# 03-SROM.net
KiCad netlist of a schematic drawn in Altium Designer
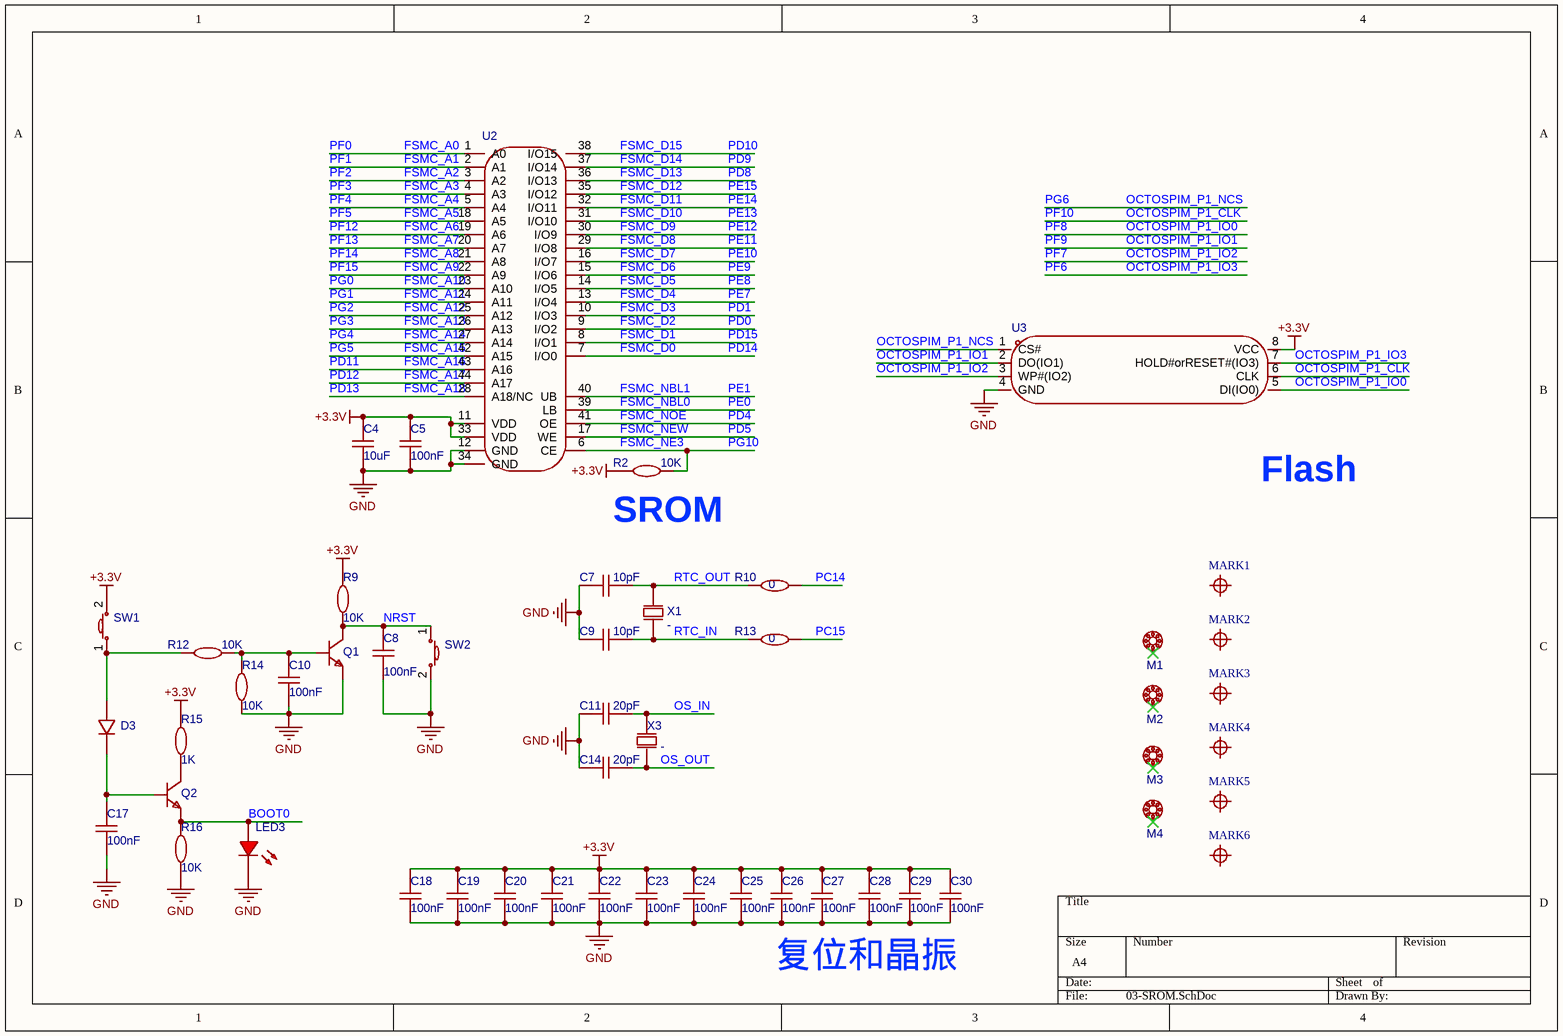
[diagram p0: 03-SROM.SchDoc]

(export (version "E")
  (design (tool "Eeschema 10.0.6"))
  (components
    (comp (ref "C4")
      (value "10uF")
      (footprint "C0603")
      (fields (field (name "Comment") "CAP_0603"))
      (libsource (lib "altium-import") (part "root_1_CAP_0603_"))
    )
    (comp (ref "C5")
      (value "100nF")
      (footprint "C0603")
      (fields (field (name "Comment") "CAP_0603"))
      (libsource (lib "altium-import") (part "root_1_CAP_0603_"))
    )
    (comp (ref "C7")
      (value "10pF")
      (footprint "C0603")
      (fields (field (name "Comment") "CAP_0603"))
      (libsource (lib "altium-import") (part "root_0_CAP_0603_"))
    )
    (comp (ref "C8")
      (value "100nF")
      (footprint "C0603")
      (fields (field (name "Comment") "CAP_0603"))
      (libsource (lib "altium-import") (part "root_1_CAP_0603_"))
    )
    (comp (ref "C9")
      (value "10pF")
      (footprint "C0603")
      (fields (field (name "Comment") "CAP_0603"))
      (libsource (lib "altium-import") (part "root_0_CAP_0603_"))
    )
    (comp (ref "C10")
      (value "100nF")
      (footprint "C0603")
      (fields (field (name "Comment") "CAP_0603"))
      (libsource (lib "altium-import") (part "root_1_CAP_0603_"))
    )
    (comp (ref "C11")
      (value "20pF")
      (footprint "C0603")
      (fields (field (name "Comment") "CAP_0603"))
      (libsource (lib "altium-import") (part "root_0_CAP_0603_"))
    )
    (comp (ref "C14")
      (value "20pF")
      (footprint "C0603")
      (fields (field (name "Comment") "CAP_0603"))
      (libsource (lib "altium-import") (part "root_0_CAP_0603_"))
    )
    (comp (ref "C17")
      (value "100nF")
      (footprint "C0603")
      (fields (field (name "Comment") "CAP_0603"))
      (libsource (lib "altium-import") (part "root_1_CAP_0603_"))
    )
    (comp (ref "C18")
      (value "100nF")
      (footprint "C0603")
      (fields (field (name "Comment") "CAP_0603"))
      (libsource (lib "altium-import") (part "root_1_CAP_0603_"))
    )
    (comp (ref "C19")
      (value "100nF")
      (footprint "C0603")
      (fields (field (name "Comment") "CAP_0603"))
      (libsource (lib "altium-import") (part "root_1_CAP_0603_"))
    )
    (comp (ref "C20")
      (value "100nF")
      (footprint "C0603")
      (fields (field (name "Comment") "CAP_0603"))
      (libsource (lib "altium-import") (part "root_1_CAP_0603_"))
    )
    (comp (ref "C21")
      (value "100nF")
      (footprint "C0603")
      (fields (field (name "Comment") "CAP_0603"))
      (libsource (lib "altium-import") (part "root_1_CAP_0603_"))
    )
    (comp (ref "C22")
      (value "100nF")
      (footprint "C0603")
      (fields (field (name "Comment") "CAP_0603"))
      (libsource (lib "altium-import") (part "root_1_CAP_0603_"))
    )
    (comp (ref "C23")
      (value "100nF")
      (footprint "C0603")
      (fields (field (name "Comment") "CAP_0603"))
      (libsource (lib "altium-import") (part "root_1_CAP_0603_"))
    )
    (comp (ref "C24")
      (value "100nF")
      (footprint "C0603")
      (fields (field (name "Comment") "CAP_0603"))
      (libsource (lib "altium-import") (part "root_1_CAP_0603_"))
    )
    (comp (ref "C25")
      (value "100nF")
      (footprint "C0603")
      (fields (field (name "Comment") "CAP_0603"))
      (libsource (lib "altium-import") (part "root_1_CAP_0603_"))
    )
    (comp (ref "C26")
      (value "100nF")
      (footprint "C0603")
      (fields (field (name "Comment") "CAP_0603"))
      (libsource (lib "altium-import") (part "root_1_CAP_0603_"))
    )
    (comp (ref "C27")
      (value "100nF")
      (footprint "C0603")
      (fields (field (name "Comment") "CAP_0603"))
      (libsource (lib "altium-import") (part "root_1_CAP_0603_"))
    )
    (comp (ref "C28")
      (value "100nF")
      (footprint "C0603")
      (fields (field (name "Comment") "CAP_0603"))
      (libsource (lib "altium-import") (part "root_1_CAP_0603_"))
    )
    (comp (ref "C29")
      (value "100nF")
      (footprint "C0603")
      (fields (field (name "Comment") "CAP_0603"))
      (libsource (lib "altium-import") (part "root_1_CAP_0603_"))
    )
    (comp (ref "C30")
      (value "100nF")
      (footprint "C0603")
      (fields (field (name "Comment") "CAP_0603"))
      (libsource (lib "altium-import") (part "root_1_CAP_0603_"))
    )
    (comp (ref "D3")
      (value "LL4148_C9808")
      (footprint "LL-34_L3.5-W1.5-RD")
      (fields (field (name "MANUFACTURER") "ST(先科)") (field (name "MANUFACTURERPART") "LL4148"))
      (libsource (lib "altium-import") (part "root_1_LL4148_C9808_"))
    )
    (comp (ref "LED3")
      (value "LED_0603-R")
      (footprint "LED_0603")
      (libsource (lib "altium-import") (part "root_3_LED_0603-R_"))
    )
    (comp (ref "M1")
      (value "M3螺丝")
      (footprint "Screw")
      (libsource (lib "altium-import") (part "root_1_M3螺丝_"))
    )
    (comp (ref "M2")
      (value "M3螺丝")
      (footprint "Screw")
      (libsource (lib "altium-import") (part "root_1_M3螺丝_"))
    )
    (comp (ref "M3")
      (value "M3螺丝")
      (footprint "Screw")
      (libsource (lib "altium-import") (part "root_1_M3螺丝_"))
    )
    (comp (ref "M4")
      (value "M3螺丝")
      (footprint "Screw")
      (libsource (lib "altium-import") (part "root_1_M3螺丝_"))
    )
    (comp (ref "MARK1")
      (value "Mark-Point")
      (footprint "Mark-Point")
      (libsource (lib "Lib") (part "Mark-Point"))
    )
    (comp (ref "MARK2")
      (value "Mark-Point")
      (footprint "Mark-Point")
      (libsource (lib "Lib") (part "Mark-Point"))
    )
    (comp (ref "MARK3")
      (value "Mark-Point")
      (footprint "Mark-Point")
      (libsource (lib "Lib") (part "Mark-Point"))
    )
    (comp (ref "MARK4")
      (value "Mark-Point")
      (footprint "Mark-Point")
      (libsource (lib "Lib") (part "Mark-Point"))
    )
    (comp (ref "MARK5")
      (value "Mark-Point")
      (footprint "Mark-Point")
      (libsource (lib "Lib") (part "Mark-Point"))
    )
    (comp (ref "MARK6")
      (value "Mark-Point")
      (footprint "Mark-Point")
      (libsource (lib "Lib") (part "Mark-Point"))
    )
    (comp (ref "Q1")
      (value "S8050_SOT_NPN")
      (footprint "S8050_SOT-23")
      (libsource (lib "altium-import") (part "root_0_S8050_SOT_NPN_"))
    )
    (comp (ref "Q2")
      (value "S8050_SOT_NPN")
      (footprint "S8050_SOT-23")
      (libsource (lib "altium-import") (part "root_0_S8050_SOT_NPN_"))
    )
    (comp (ref "R2")
      (value "10K")
      (footprint "R0603")
      (fields (field (name "Comment") "Res_0603"))
      (libsource (lib "altium-import") (part "root_2_Res_0603_"))
    )
    (comp (ref "R9")
      (value "10K")
      (footprint "R0603")
      (fields (field (name "Comment") "Res_0603"))
      (libsource (lib "altium-import") (part "root_1_Res_0603_"))
    )
    (comp (ref "R10")
      (value "0")
      (footprint "R0402")
      (fields (field (name "Comment") "Res_0402"))
      (libsource (lib "altium-import") (part "root_0_Res_0402_"))
    )
    (comp (ref "R12")
      (value "10K")
      (footprint "R0603")
      (fields (field (name "Comment") "Res_0603"))
      (libsource (lib "altium-import") (part "root_0_Res_0603_"))
    )
    (comp (ref "R13")
      (value "0")
      (footprint "R0402")
      (fields (field (name "Comment") "Res_0402"))
      (libsource (lib "altium-import") (part "root_0_Res_0402_"))
    )
    (comp (ref "R14")
      (value "10K")
      (footprint "R0603")
      (fields (field (name "Comment") "Res_0603"))
      (libsource (lib "altium-import") (part "root_1_Res_0603_"))
    )
    (comp (ref "R15")
      (value "1K")
      (footprint "R0603")
      (fields (field (name "Comment") "Res_0603"))
      (libsource (lib "altium-import") (part "root_1_Res_0603_"))
    )
    (comp (ref "R16")
      (value "10K")
      (footprint "R0603")
      (fields (field (name "Comment") "Res_0603"))
      (libsource (lib "altium-import") (part "root_1_Res_0603_"))
    )
    (comp (ref "SW1")
      (value "~")
      (footprint "Key_SMD_3.6x6.1x2.5")
      (libsource (lib "altium-import") (part "root_1_Key_SMD_3.6x6.1x2.5_"))
    )
    (comp (ref "SW2")
      (value "~")
      (footprint "Key_SMD_3.6x6.1x2.5")
      (libsource (lib "altium-import") (part "root_3_Key_SMD_3.6x6.1x2.5_"))
    )
    (comp (ref "U2")
      (value "IS62WV51216")
      (footprint "TSOP-44")
      (libsource (lib "altium-import") (part "root_0_IS62WV51216_"))
    )
    (comp (ref "U3")
      (value "W25Q128JVSIQ_C113767")
      (footprint "SOIC-8_L5.3-W5.3-P1.27-LS8.0-BL")
      (fields (field (name "MANUFACTURER") "WINBOND(华邦)") (field (name "MANUFACTURERPART") "W25Q128JVSIQ"))
      (libsource (lib "altium-import") (part "root_0_W25Q128JVSIQ_C113767_"))
    )
    (comp (ref "X1")
      (value "-")
      (footprint "OSC-TH_BD2.1-P0.70-D0.3")
      (description "频率:-;负载电容:-;")
      (fields (field (name "MANUFACTURER") "KDS(大真空)") (field (name "MANUFACTURERPART") "1TD125BFNS001"))
      (libsource (lib "altium-import") (part "root_1_1TD125BFNS001_"))
    )
    (comp (ref "X3")
      (value "-")
      (footprint "HC-49S_L11.4-W4.8")
      (description "频率:-;负载电容:-;")
      (fields (field (name "MANUFACTURER") "TXC(晶技)") (field (name "MANUFACTURERPART") "9C08000003"))
      (libsource (lib "altium-import") (part "root_1_9C08000003_"))
    )
  )
  (nets
    (net (code "1") (name "+3.3V") (class "Default")
      (node (ref "C18") (pin "2") (pinfunction "2_2") (pintype "passive"))
      (node (ref "C19") (pin "2") (pinfunction "2_2") (pintype "passive"))
      (node (ref "C20") (pin "2") (pinfunction "2_2") (pintype "passive"))
      (node (ref "C21") (pin "2") (pinfunction "2_2") (pintype "passive"))
      (node (ref "C22") (pin "2") (pinfunction "2_2") (pintype "passive"))
      (node (ref "C23") (pin "2") (pinfunction "2_2") (pintype "passive"))
      (node (ref "C24") (pin "2") (pinfunction "2_2") (pintype "passive"))
      (node (ref "C25") (pin "2") (pinfunction "2_2") (pintype "passive"))
      (node (ref "C26") (pin "2") (pinfunction "2_2") (pintype "passive"))
      (node (ref "C27") (pin "2") (pinfunction "2_2") (pintype "passive"))
      (node (ref "C28") (pin "2") (pinfunction "2_2") (pintype "passive"))
      (node (ref "C29") (pin "2") (pinfunction "2_2") (pintype "passive"))
      (node (ref "C30") (pin "2") (pinfunction "2_2") (pintype "passive"))
      (node (ref "C4") (pin "2") (pinfunction "2_2") (pintype "passive"))
      (node (ref "C5") (pin "2") (pinfunction "2_2") (pintype "passive"))
      (node (ref "R15") (pin "2") (pinfunction "2_2") (pintype "passive"))
      (node (ref "R2") (pin "2") (pinfunction "2_2") (pintype "passive"))
      (node (ref "R9") (pin "2") (pinfunction "2_2") (pintype "passive"))
      (node (ref "SW1") (pin "2") (pinfunction "2_2") (pintype "passive"))
      (node (ref "U2") (pin "11") (pinfunction "VDD_11") (pintype "passive"))
      (node (ref "U2") (pin "33") (pinfunction "VDD_33") (pintype "passive"))
      (node (ref "U3") (pin "8") (pinfunction "VCC_8") (pintype "passive"))
    )
    (net (code "2") (name "/BOOT0") (class "Default")
      (node (ref "LED3") (pin "2") (pinfunction "A_2") (pintype "passive"))
      (node (ref "Q2") (pin "2") (pinfunction "2_2") (pintype "passive"))
      (node (ref "R16") (pin "2") (pinfunction "2_2") (pintype "passive"))
    )
    (net (code "3") (name "/FSMC_A0") (class "Default")
      (node (ref "U2") (pin "1") (pinfunction "A0_1") (pintype "passive"))
    )
    (net (code "4") (name "/FSMC_A1") (class "Default")
      (node (ref "U2") (pin "2") (pinfunction "A1_2") (pintype "passive"))
    )
    (net (code "5") (name "/FSMC_A2") (class "Default")
      (node (ref "U2") (pin "3") (pinfunction "A2_3") (pintype "passive"))
    )
    (net (code "6") (name "/FSMC_A3") (class "Default")
      (node (ref "U2") (pin "4") (pinfunction "A3_4") (pintype "passive"))
    )
    (net (code "7") (name "/FSMC_A4") (class "Default")
      (node (ref "U2") (pin "5") (pinfunction "A4_5") (pintype "passive"))
    )
    (net (code "8") (name "/FSMC_A5") (class "Default")
      (node (ref "U2") (pin "18") (pinfunction "A5_18") (pintype "passive"))
    )
    (net (code "9") (name "/FSMC_A6") (class "Default")
      (node (ref "U2") (pin "19") (pinfunction "A6_19") (pintype "passive"))
    )
    (net (code "10") (name "/FSMC_A7") (class "Default")
      (node (ref "U2") (pin "20") (pinfunction "A7_20") (pintype "passive"))
    )
    (net (code "11") (name "/FSMC_A8") (class "Default")
      (node (ref "U2") (pin "21") (pinfunction "A8_21") (pintype "passive"))
    )
    (net (code "12") (name "/FSMC_A9") (class "Default")
      (node (ref "U2") (pin "22") (pinfunction "A9_22") (pintype "passive"))
    )
    (net (code "13") (name "/FSMC_A10") (class "Default")
      (node (ref "U2") (pin "23") (pinfunction "A10_23") (pintype "passive"))
    )
    (net (code "14") (name "/FSMC_A11") (class "Default")
      (node (ref "U2") (pin "24") (pinfunction "A11_24") (pintype "passive"))
    )
    (net (code "15") (name "/FSMC_A12") (class "Default")
      (node (ref "U2") (pin "25") (pinfunction "A12_25") (pintype "passive"))
    )
    (net (code "16") (name "/FSMC_A13") (class "Default")
      (node (ref "U2") (pin "26") (pinfunction "A13_26") (pintype "passive"))
    )
    (net (code "17") (name "/FSMC_A14") (class "Default")
      (node (ref "U2") (pin "27") (pinfunction "A14_27") (pintype "passive"))
    )
    (net (code "18") (name "/FSMC_A15") (class "Default")
      (node (ref "U2") (pin "42") (pinfunction "A15_42") (pintype "passive"))
    )
    (net (code "19") (name "/FSMC_A16") (class "Default")
      (node (ref "U2") (pin "43") (pinfunction "A16_43") (pintype "passive"))
    )
    (net (code "20") (name "/FSMC_A17") (class "Default")
      (node (ref "U2") (pin "44") (pinfunction "A17_44") (pintype "passive"))
    )
    (net (code "21") (name "/FSMC_A18") (class "Default")
      (node (ref "U2") (pin "28") (pinfunction "A18/NC_28") (pintype "passive"))
    )
    (net (code "22") (name "/FSMC_D0") (class "Default")
      (node (ref "U2") (pin "7") (pinfunction "I/O0_7") (pintype "passive"))
    )
    (net (code "23") (name "/FSMC_D1") (class "Default")
      (node (ref "U2") (pin "8") (pinfunction "I/O1_8") (pintype "passive"))
    )
    (net (code "24") (name "/FSMC_D2") (class "Default")
      (node (ref "U2") (pin "9") (pinfunction "I/O2_9") (pintype "passive"))
    )
    (net (code "25") (name "/FSMC_D3") (class "Default")
      (node (ref "U2") (pin "10") (pinfunction "I/O3_10") (pintype "passive"))
    )
    (net (code "26") (name "/FSMC_D4") (class "Default")
      (node (ref "U2") (pin "13") (pinfunction "I/O4_13") (pintype "passive"))
    )
    (net (code "27") (name "/FSMC_D5") (class "Default")
      (node (ref "U2") (pin "14") (pinfunction "I/O5_14") (pintype "passive"))
    )
    (net (code "28") (name "/FSMC_D6") (class "Default")
      (node (ref "U2") (pin "15") (pinfunction "I/O6_15") (pintype "passive"))
    )
    (net (code "29") (name "/FSMC_D7") (class "Default")
      (node (ref "U2") (pin "16") (pinfunction "I/O7_16") (pintype "passive"))
    )
    (net (code "30") (name "/FSMC_D8") (class "Default")
      (node (ref "U2") (pin "29") (pinfunction "I/O8_29") (pintype "passive"))
    )
    (net (code "31") (name "/FSMC_D9") (class "Default")
      (node (ref "U2") (pin "30") (pinfunction "I/O9_30") (pintype "passive"))
    )
    (net (code "32") (name "/FSMC_D10") (class "Default")
      (node (ref "U2") (pin "31") (pinfunction "I/O10_31") (pintype "passive"))
    )
    (net (code "33") (name "/FSMC_D11") (class "Default")
      (node (ref "U2") (pin "32") (pinfunction "I/O11_32") (pintype "passive"))
    )
    (net (code "34") (name "/FSMC_D12") (class "Default")
      (node (ref "U2") (pin "35") (pinfunction "I/O12_35") (pintype "passive"))
    )
    (net (code "35") (name "/FSMC_D13") (class "Default")
      (node (ref "U2") (pin "36") (pinfunction "I/O13_36") (pintype "passive"))
    )
    (net (code "36") (name "/FSMC_D14") (class "Default")
      (node (ref "U2") (pin "37") (pinfunction "I/O14_37") (pintype "passive"))
    )
    (net (code "37") (name "/FSMC_D15") (class "Default")
      (node (ref "U2") (pin "38") (pinfunction "I/O15_38") (pintype "passive"))
    )
    (net (code "38") (name "/FSMC_NBL0") (class "Default")
      (node (ref "U2") (pin "39") (pinfunction "LB_39") (pintype "passive"))
    )
    (net (code "39") (name "/FSMC_NBL1") (class "Default")
      (node (ref "U2") (pin "40") (pinfunction "UB_40") (pintype "passive"))
    )
    (net (code "40") (name "/FSMC_NE3") (class "Default")
      (node (ref "R2") (pin "1") (pinfunction "1_1") (pintype "passive"))
      (node (ref "U2") (pin "6") (pinfunction "CE_6") (pintype "passive"))
    )
    (net (code "41") (name "/FSMC_NEW") (class "Default")
      (node (ref "U2") (pin "17") (pinfunction "WE_17") (pintype "passive"))
    )
    (net (code "42") (name "/FSMC_NOE") (class "Default")
      (node (ref "U2") (pin "41") (pinfunction "OE_41") (pintype "passive"))
    )
    (net (code "43") (name "/NRST") (class "Default")
      (node (ref "C8") (pin "2") (pinfunction "2_2") (pintype "passive"))
      (node (ref "Q1") (pin "3") (pinfunction "3_3") (pintype "passive"))
      (node (ref "R9") (pin "1") (pinfunction "1_1") (pintype "passive"))
      (node (ref "SW2") (pin "1") (pinfunction "1_1") (pintype "passive"))
    )
    (net (code "44") (name "/OCTOSPIM_P1_CLK") (class "Default")
      (node (ref "U3") (pin "6") (pinfunction "CLK_6") (pintype "passive"))
    )
    (net (code "45") (name "/OCTOSPIM_P1_IO0") (class "Default")
      (node (ref "U3") (pin "5") (pinfunction "DI(IO0)_5") (pintype "passive"))
    )
    (net (code "46") (name "/OCTOSPIM_P1_IO1") (class "Default")
      (node (ref "U3") (pin "2") (pinfunction "DO(IO1)_2") (pintype "passive"))
    )
    (net (code "47") (name "/OCTOSPIM_P1_IO2") (class "Default")
      (node (ref "U3") (pin "3") (pinfunction "WP#(IO2)_3") (pintype "passive"))
    )
    (net (code "48") (name "/OCTOSPIM_P1_IO3") (class "Default")
      (node (ref "U3") (pin "7") (pinfunction "HOLD#orRESET#(IO3)_7") (pintype "passive"))
    )
    (net (code "49") (name "/OCTOSPIM_P1_NCS") (class "Default")
      (node (ref "U3") (pin "1") (pinfunction "CS#_1") (pintype "passive"))
    )
    (net (code "50") (name "/OS_IN") (class "Default")
      (node (ref "C11") (pin "2") (pinfunction "2_2") (pintype "passive"))
      (node (ref "X3") (pin "2") (pinfunction "OSC2_2") (pintype "passive"))
    )
    (net (code "51") (name "/OS_OUT") (class "Default")
      (node (ref "C14") (pin "2") (pinfunction "2_2") (pintype "passive"))
      (node (ref "X3") (pin "1") (pinfunction "OSC1_1") (pintype "passive"))
    )
    (net (code "52") (name "/PC14") (class "Default")
      (node (ref "R10") (pin "2") (pinfunction "2_2") (pintype "passive"))
    )
    (net (code "53") (name "/PC15") (class "Default")
      (node (ref "R13") (pin "2") (pinfunction "2_2") (pintype "passive"))
    )
    (net (code "54") (name "/RTC_IN") (class "Default")
      (node (ref "C9") (pin "2") (pinfunction "2_2") (pintype "passive"))
      (node (ref "R13") (pin "1") (pinfunction "1_1") (pintype "passive"))
      (node (ref "X1") (pin "2") (pinfunction "OSC2_2") (pintype "passive"))
    )
    (net (code "55") (name "/RTC_OUT") (class "Default")
      (node (ref "C7") (pin "2") (pinfunction "2_2") (pintype "passive"))
      (node (ref "R10") (pin "1") (pinfunction "1_1") (pintype "passive"))
      (node (ref "X1") (pin "1") (pinfunction "OSC1_1") (pintype "passive"))
    )
    (net (code "56") (name "GND") (class "Default")
      (node (ref "C10") (pin "1") (pinfunction "1_1") (pintype "passive"))
      (node (ref "C11") (pin "1") (pinfunction "1_1") (pintype "passive"))
      (node (ref "C14") (pin "1") (pinfunction "1_1") (pintype "passive"))
      (node (ref "C17") (pin "1") (pinfunction "1_1") (pintype "passive"))
      (node (ref "C18") (pin "1") (pinfunction "1_1") (pintype "passive"))
      (node (ref "C19") (pin "1") (pinfunction "1_1") (pintype "passive"))
      (node (ref "C20") (pin "1") (pinfunction "1_1") (pintype "passive"))
      (node (ref "C21") (pin "1") (pinfunction "1_1") (pintype "passive"))
      (node (ref "C22") (pin "1") (pinfunction "1_1") (pintype "passive"))
      (node (ref "C23") (pin "1") (pinfunction "1_1") (pintype "passive"))
      (node (ref "C24") (pin "1") (pinfunction "1_1") (pintype "passive"))
      (node (ref "C25") (pin "1") (pinfunction "1_1") (pintype "passive"))
      (node (ref "C26") (pin "1") (pinfunction "1_1") (pintype "passive"))
      (node (ref "C27") (pin "1") (pinfunction "1_1") (pintype "passive"))
      (node (ref "C28") (pin "1") (pinfunction "1_1") (pintype "passive"))
      (node (ref "C29") (pin "1") (pinfunction "1_1") (pintype "passive"))
      (node (ref "C30") (pin "1") (pinfunction "1_1") (pintype "passive"))
      (node (ref "C4") (pin "1") (pinfunction "1_1") (pintype "passive"))
      (node (ref "C5") (pin "1") (pinfunction "1_1") (pintype "passive"))
      (node (ref "C7") (pin "1") (pinfunction "1_1") (pintype "passive"))
      (node (ref "C8") (pin "1") (pinfunction "1_1") (pintype "passive"))
      (node (ref "C9") (pin "1") (pinfunction "1_1") (pintype "passive"))
      (node (ref "LED3") (pin "1") (pinfunction "C_1") (pintype "passive"))
      (node (ref "Q1") (pin "2") (pinfunction "2_2") (pintype "passive"))
      (node (ref "R14") (pin "1") (pinfunction "1_1") (pintype "passive"))
      (node (ref "R16") (pin "1") (pinfunction "1_1") (pintype "passive"))
      (node (ref "SW2") (pin "2") (pinfunction "2_2") (pintype "passive"))
      (node (ref "U2") (pin "12") (pinfunction "GND_12") (pintype "passive"))
      (node (ref "U2") (pin "34") (pinfunction "GND_34") (pintype "passive"))
      (node (ref "U3") (pin "4") (pinfunction "GND_4") (pintype "passive"))
    )
    (net (code "57") (name "Net-(C10-Pad2)") (class "Default")
      (node (ref "C10") (pin "2") (pinfunction "2_2") (pintype "passive"))
      (node (ref "Q1") (pin "1") (pinfunction "1_1") (pintype "passive"))
      (node (ref "R12") (pin "2") (pinfunction "2_2") (pintype "passive"))
      (node (ref "R14") (pin "2") (pinfunction "2_2") (pintype "passive"))
    )
    (net (code "58") (name "Net-(D3-A)") (class "Default")
      (node (ref "D3") (pin "2") (pinfunction "A_2") (pintype "passive"))
      (node (ref "R12") (pin "1") (pinfunction "1_1") (pintype "passive"))
      (node (ref "SW1") (pin "1") (pinfunction "1_1") (pintype "passive"))
    )
    (net (code "59") (name "Net-(D3-K)") (class "Default")
      (node (ref "C17") (pin "2") (pinfunction "2_2") (pintype "passive"))
      (node (ref "D3") (pin "1") (pinfunction "K_1") (pintype "passive"))
      (node (ref "Q2") (pin "1") (pinfunction "1_1") (pintype "passive"))
    )
    (net (code "60") (name "Net-(Q2-Pad3)") (class "Default")
      (node (ref "Q2") (pin "3") (pinfunction "3_3") (pintype "passive"))
      (node (ref "R15") (pin "1") (pinfunction "1_1") (pintype "passive"))
    )
    (net (code "61") (name "unconnected-(M1-Pad1)") (class "Default")
      (node (ref "M1") (pin "1") (pinfunction "1_1") (pintype "passive+no_connect"))
    )
    (net (code "62") (name "unconnected-(M2-Pad1)") (class "Default")
      (node (ref "M2") (pin "1") (pinfunction "1_1") (pintype "passive+no_connect"))
    )
    (net (code "63") (name "unconnected-(M3-Pad1)") (class "Default")
      (node (ref "M3") (pin "1") (pinfunction "1_1") (pintype "passive+no_connect"))
    )
    (net (code "64") (name "unconnected-(M4-Pad1)") (class "Default")
      (node (ref "M4") (pin "1") (pinfunction "1_1") (pintype "passive+no_connect"))
    )
    (net (code "65") (name "unconnected-(MARK1-Pad1)") (class "Default")
      (node (ref "MARK1") (pin "1") (pinfunction "1_1") (pintype "passive"))
    )
    (net (code "66") (name "unconnected-(MARK2-Pad1)") (class "Default")
      (node (ref "MARK2") (pin "1") (pinfunction "1_1") (pintype "passive"))
    )
    (net (code "67") (name "unconnected-(MARK3-Pad1)") (class "Default")
      (node (ref "MARK3") (pin "1") (pinfunction "1_1") (pintype "passive"))
    )
    (net (code "68") (name "unconnected-(MARK4-Pad1)") (class "Default")
      (node (ref "MARK4") (pin "1") (pinfunction "1_1") (pintype "passive"))
    )
    (net (code "69") (name "unconnected-(MARK5-Pad1)") (class "Default")
      (node (ref "MARK5") (pin "1") (pinfunction "1_1") (pintype "passive"))
    )
    (net (code "70") (name "unconnected-(MARK6-Pad1)") (class "Default")
      (node (ref "MARK6") (pin "1") (pinfunction "1_1") (pintype "passive"))
    )
  )
)
